# Portas_Logicas.net
KiCad netlist of a schematic drawn in EasyEDA Pro
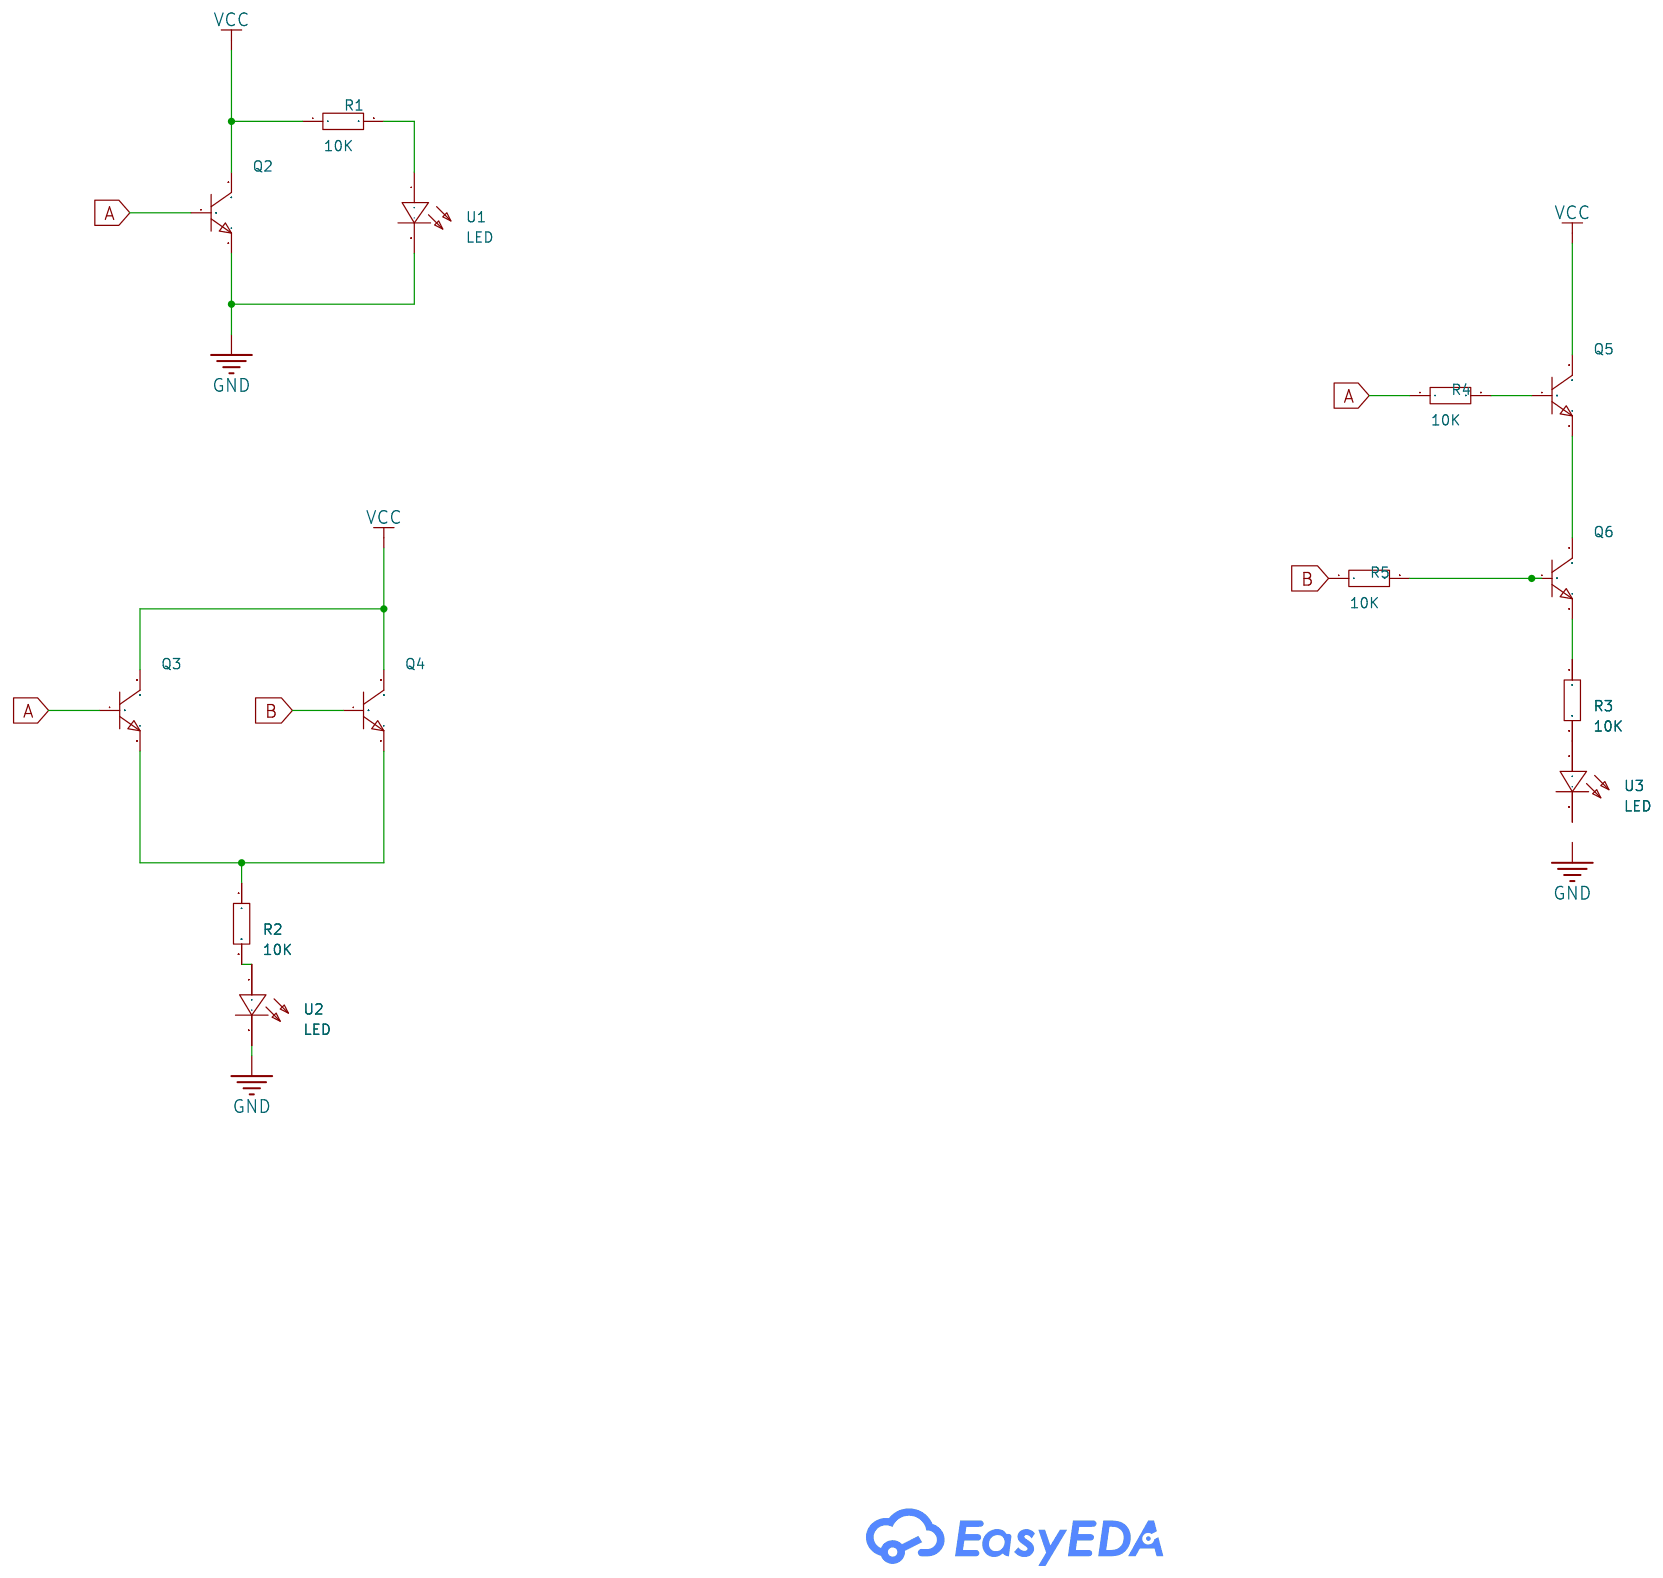
[diagram p0: schematic sheet]

(export (version "E")
  (design (tool "Eeschema 10.0.6"))
  (components
    (comp (ref "Q2")
      (value "~")
      (footprint "easyedapro:SOT-23_L2.9-W1.3-P1.90-LS2.4-BR")
      (libsource (lib "easyedapro") (part "NPN"))
    )
    (comp (ref "Q3")
      (value "~")
      (footprint "easyedapro:SOT-23_L2.9-W1.3-P1.90-LS2.4-BR")
      (libsource (lib "easyedapro") (part "NPN"))
    )
    (comp (ref "Q4")
      (value "~")
      (footprint "easyedapro:SOT-23_L2.9-W1.3-P1.90-LS2.4-BR")
      (libsource (lib "easyedapro") (part "NPN"))
    )
    (comp (ref "Q5")
      (value "~")
      (footprint "easyedapro:SOT-23_L2.9-W1.3-P1.90-LS2.4-BR")
      (libsource (lib "easyedapro") (part "NPN"))
    )
    (comp (ref "Q6")
      (value "~")
      (footprint "easyedapro:SOT-23_L2.9-W1.3-P1.90-LS2.4-BR")
      (libsource (lib "easyedapro") (part "NPN"))
    )
    (comp (ref "R1") (value "10K") (footprint "easyedapro:R0603") (libsource (lib "easyedapro") (part "Res")))
    (comp (ref "R2") (value "10K") (footprint "easyedapro:R0603") (libsource (lib "easyedapro") (part "Res")))
    (comp (ref "R3") (value "10K") (footprint "easyedapro:R0603") (libsource (lib "easyedapro") (part "Res")))
    (comp (ref "R4") (value "10K") (footprint "easyedapro:R0603") (libsource (lib "easyedapro") (part "Res")))
    (comp (ref "R5") (value "10K") (footprint "easyedapro:R0603") (libsource (lib "easyedapro") (part "Res")))
    (comp (ref "U1")
      (value "LED")
      (footprint "easyedapro:LED-TH_BD4.0-P2.54-FD_RED")
      (libsource (lib "easyedapro") (part "LED_C9900015665"))
    )
    (comp (ref "U2")
      (value "LED")
      (footprint "easyedapro:LED-TH_BD4.0-P2.54-FD_RED")
      (libsource (lib "easyedapro") (part "LED_C9900015665"))
    )
    (comp (ref "U3")
      (value "LED")
      (footprint "easyedapro:LED-TH_BD4.0-P2.54-FD_RED")
      (libsource (lib "easyedapro") (part "LED_C9900015665"))
    )
  )
  (nets
    (net (code "1") (name "A") (class "Default")
      (node (ref "Q2") (pin "1") (pinfunction "B_1") (pintype "unspecified"))
      (node (ref "Q3") (pin "1") (pinfunction "B_1") (pintype "unspecified"))
      (node (ref "R4") (pin "1") (pinfunction "1_1") (pintype "input"))
    )
    (net (code "2") (name "B") (class "Default")
      (node (ref "Q4") (pin "1") (pinfunction "B_1") (pintype "unspecified"))
      (node (ref "R5") (pin "1") (pinfunction "1_1") (pintype "input"))
    )
    (net (code "3") (name "GND") (class "Default")
      (node (ref "Q2") (pin "2") (pinfunction "E_2") (pintype "unspecified"))
      (node (ref "U1") (pin "2") (pinfunction "-_2") (pintype "unspecified"))
      (node (ref "U2") (pin "2") (pinfunction "-_2") (pintype "unspecified"))
    )
    (net (code "4") (name "Net-(Q3-E)") (class "Default")
      (node (ref "Q3") (pin "2") (pinfunction "E_2") (pintype "unspecified"))
      (node (ref "Q4") (pin "2") (pinfunction "E_2") (pintype "unspecified"))
      (node (ref "R2") (pin "1") (pinfunction "1_1") (pintype "input"))
    )
    (net (code "5") (name "Net-(Q5-B)") (class "Default")
      (node (ref "Q5") (pin "1") (pinfunction "B_1") (pintype "unspecified"))
      (node (ref "R4") (pin "2") (pinfunction "2_2") (pintype "input"))
    )
    (net (code "6") (name "Net-(Q5-E)") (class "Default")
      (node (ref "Q5") (pin "2") (pinfunction "E_2") (pintype "unspecified"))
      (node (ref "Q6") (pin "3") (pinfunction "C_3") (pintype "unspecified"))
    )
    (net (code "7") (name "Net-(Q6-B)") (class "Default")
      (node (ref "Q6") (pin "1") (pinfunction "B_1") (pintype "unspecified"))
      (node (ref "R5") (pin "2") (pinfunction "2_2") (pintype "input"))
    )
    (net (code "8") (name "Net-(Q6-E)") (class "Default")
      (node (ref "Q6") (pin "2") (pinfunction "E_2") (pintype "unspecified"))
      (node (ref "R3") (pin "1") (pinfunction "1_1") (pintype "input"))
    )
    (net (code "9") (name "Net-(U1-+)") (class "Default")
      (node (ref "R1") (pin "2") (pinfunction "2_2") (pintype "input"))
      (node (ref "U1") (pin "1") (pinfunction "+_1") (pintype "unspecified"))
    )
    (net (code "10") (name "Net-(U2-+)") (class "Default")
      (node (ref "R2") (pin "2") (pinfunction "2_2") (pintype "input"))
      (node (ref "U2") (pin "1") (pinfunction "+_1") (pintype "unspecified"))
    )
    (net (code "11") (name "Net-(U3-+)") (class "Default")
      (node (ref "R3") (pin "2") (pinfunction "2_2") (pintype "input"))
      (node (ref "U3") (pin "1") (pinfunction "+_1") (pintype "unspecified"))
    )
    (net (code "12") (name "VCC") (class "Default")
      (node (ref "Q2") (pin "3") (pinfunction "C_3") (pintype "unspecified"))
      (node (ref "Q3") (pin "3") (pinfunction "C_3") (pintype "unspecified"))
      (node (ref "Q4") (pin "3") (pinfunction "C_3") (pintype "unspecified"))
      (node (ref "Q5") (pin "3") (pinfunction "C_3") (pintype "unspecified"))
      (node (ref "R1") (pin "1") (pinfunction "1_1") (pintype "input"))
    )
    (net (code "13") (name "unconnected-(U3---Pad2)") (class "Default")
      (node (ref "U3") (pin "2") (pinfunction "-_2") (pintype "unspecified"))
    )
  )
)
